# BEAMFORMER.net
KiCad netlist of a schematic drawn in Altium Designer
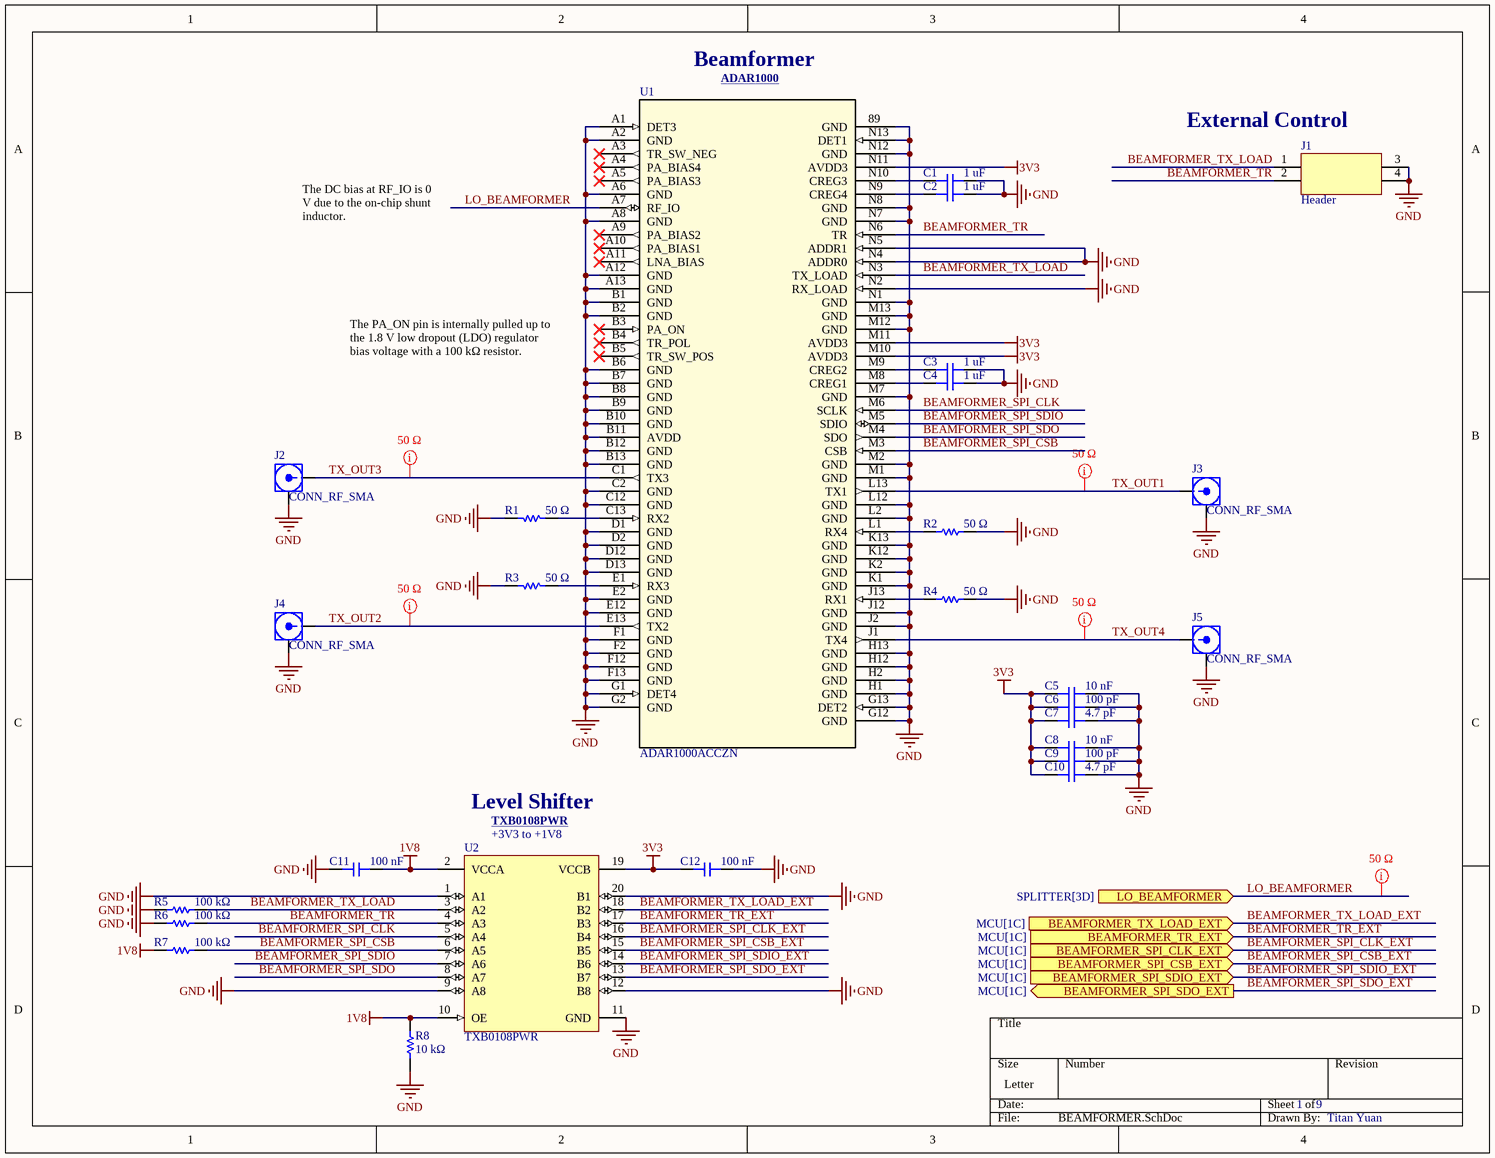
[diagram p0: BEAMFORMER.SchDoc]

(export (version "E")
  (design (tool "Eeschema 10.0.6"))
  (components
    (comp (ref "C1")
      (value "1 uF")
      (footprint "CAP_0603")
      (description "25V 1uF X7R ±10% 0603 Multilayer Ceramic Capacitors MLCC - SMD/SMT ROHS")
      (fields
        (field (name "MANUFACTURER") "Samsung Electro-Mechanics")
        (field (name "MANUFACTURER PART NUMBER") "CL10B105KA8NNNC")
      )
      (libsource (lib "Titan") (part "CAP"))
    )
    (comp (ref "C2")
      (value "1 uF")
      (footprint "CAP_0603")
      (description "25V 1uF X7R ±10% 0603 Multilayer Ceramic Capacitors MLCC - SMD/SMT ROHS")
      (fields
        (field (name "MANUFACTURER") "Samsung Electro-Mechanics")
        (field (name "MANUFACTURER PART NUMBER") "CL10B105KA8NNNC")
      )
      (libsource (lib "Titan") (part "CAP"))
    )
    (comp (ref "C3")
      (value "1 uF")
      (footprint "CAP_0603")
      (description "25V 1uF X7R ±10% 0603 Multilayer Ceramic Capacitors MLCC - SMD/SMT ROHS")
      (fields
        (field (name "MANUFACTURER") "Samsung Electro-Mechanics")
        (field (name "MANUFACTURER PART NUMBER") "CL10B105KA8NNNC")
      )
      (libsource (lib "Titan") (part "CAP"))
    )
    (comp (ref "C4")
      (value "1 uF")
      (footprint "CAP_0603")
      (description "25V 1uF X7R ±10% 0603 Multilayer Ceramic Capacitors MLCC - SMD/SMT ROHS")
      (fields
        (field (name "MANUFACTURER") "Samsung Electro-Mechanics")
        (field (name "MANUFACTURER PART NUMBER") "CL10B105KA8NNNC")
      )
      (libsource (lib "Titan") (part "CAP"))
    )
    (comp (ref "C5")
      (value "10 nF")
      (footprint "CAP_0402")
      (description "Multilayer Ceramic Capacitor, 0.01 uF, 25 V, ± 10%, X7R, 0402 [1005 Metric]")
      (fields
        (field (name "MANUFACTURER") "Murata Electronics")
        (field (name "MANUFACTURER PART NUMBER") "GRM155R71E103KA01D")
      )
      (libsource (lib "Titan") (part "CAP"))
    )
    (comp (ref "C6")
      (value "100 pF")
      (footprint "CAP_0402")
      (description "50V 100pF NP0 ±5% 0402 Multilayer Ceramic Capacitors MLCC - SMD/SMT ROHS")
      (fields
        (field (name "MANUFACTURER") "Yageo")
        (field (name "MANUFACTURER PART NUMBER") "CC0402JRNPO9BN101")
      )
      (libsource (lib "Titan") (part "CAP"))
    )
    (comp (ref "C7")
      (value "4.7 pF")
      (footprint "CAP_0402")
      (description "0402 4.7 pF 50 V ±0.25 pF Tolerance C0G SMT Multilayer Ceramic Capacitor")
      (fields
        (field (name "MANUFACTURER") "Murata Electronics")
        (field (name "MANUFACTURER PART NUMBER") "GRM1555C1H4R7CA01D")
      )
      (libsource (lib "Titan") (part "CAP"))
    )
    (comp (ref "C8")
      (value "10 nF")
      (footprint "CAP_0402")
      (description "Multilayer Ceramic Capacitor, 0.01 uF, 25 V, ± 10%, X7R, 0402 [1005 Metric]")
      (fields
        (field (name "MANUFACTURER") "Murata Electronics")
        (field (name "MANUFACTURER PART NUMBER") "GRM155R71E103KA01D")
      )
      (libsource (lib "Titan") (part "CAP"))
    )
    (comp (ref "C9")
      (value "100 pF")
      (footprint "CAP_0402")
      (description "50V 100pF NP0 ±5% 0402 Multilayer Ceramic Capacitors MLCC - SMD/SMT ROHS")
      (fields
        (field (name "MANUFACTURER") "Yageo")
        (field (name "MANUFACTURER PART NUMBER") "CC0402JRNPO9BN101")
      )
      (libsource (lib "Titan") (part "CAP"))
    )
    (comp (ref "C10")
      (value "4.7 pF")
      (footprint "CAP_0402")
      (description "0402 4.7 pF 50 V ±0.25 pF Tolerance C0G SMT Multilayer Ceramic Capacitor")
      (fields
        (field (name "MANUFACTURER") "Murata Electronics")
        (field (name "MANUFACTURER PART NUMBER") "GRM1555C1H4R7CA01D")
      )
      (libsource (lib "Titan") (part "CAP"))
    )
    (comp (ref "C11")
      (value "100 nF")
      (footprint "CAP_0402")
      (description "Ceramic Capacitor, Ceramic, 50V, 10% +Tol, 10% -Tol, X7R, 15% TC, 0.1uF, Surface Mount, 0402")
      (fields
        (field (name "MANUFACTURER") "Yageo")
        (field (name "MANUFACTURER PART NUMBER") "CC0402KPX7R9BB104")
      )
      (libsource (lib "Titan") (part "CAP"))
    )
    (comp (ref "C12")
      (value "100 nF")
      (footprint "CAP_0402")
      (description "Ceramic Capacitor, Ceramic, 50V, 10% +Tol, 10% -Tol, X7R, 15% TC, 0.1uF, Surface Mount, 0402")
      (fields
        (field (name "MANUFACTURER") "Yageo")
        (field (name "MANUFACTURER PART NUMBER") "CC0402KPX7R9BB104")
      )
      (libsource (lib "Titan") (part "CAP"))
    )
    (comp (ref "J1")
      (value "Header")
      (footprint "CONN_2x2_2.54mm_PinHeader_Vertical")
      (description "Pin Header, Board-to-Board, 2.54 mm, 2 Rows, 4 Contacts, Through Hole, TSW Series")
      (fields
        (field (name "MANUFACTURER") "Samtec")
        (field (name "MANUFACTURER PART NUMBER") "TSW-102-07-F-D")
      )
      (libsource (lib "Titan") (part "CONN_2x2_2.54mm_PinHeader_Vertical"))
    )
    (comp (ref "J2")
      (value "CONN_RF_SMA")
      (footprint "142-0701-801")
      (description "RF / Coaxial Connector, SMA Coaxial, Straight Jack, Solder, 50 ohm, Beryllium Copper")
      (fields
        (field (name "MANUFACTURER") "Cinch Connectivity Solutions Johnson")
        (field (name "MANUFACTURER PART NUMBER") "142-0701-801")
      )
      (libsource (lib "Titan") (part "CONN_RF_SMA"))
    )
    (comp (ref "J3")
      (value "CONN_RF_SMA")
      (footprint "142-0701-801")
      (description "RF / Coaxial Connector, SMA Coaxial, Straight Jack, Solder, 50 ohm, Beryllium Copper")
      (fields
        (field (name "MANUFACTURER") "Cinch Connectivity Solutions Johnson")
        (field (name "MANUFACTURER PART NUMBER") "142-0701-801")
      )
      (libsource (lib "Titan") (part "CONN_RF_SMA"))
    )
    (comp (ref "J4")
      (value "CONN_RF_SMA")
      (footprint "142-0701-801")
      (description "RF / Coaxial Connector, SMA Coaxial, Straight Jack, Solder, 50 ohm, Beryllium Copper")
      (fields
        (field (name "MANUFACTURER") "Cinch Connectivity Solutions Johnson")
        (field (name "MANUFACTURER PART NUMBER") "142-0701-801")
      )
      (libsource (lib "Titan") (part "CONN_RF_SMA"))
    )
    (comp (ref "J5")
      (value "CONN_RF_SMA")
      (footprint "142-0701-801")
      (description "RF / Coaxial Connector, SMA Coaxial, Straight Jack, Solder, 50 ohm, Beryllium Copper")
      (fields
        (field (name "MANUFACTURER") "Cinch Connectivity Solutions Johnson")
        (field (name "MANUFACTURER PART NUMBER") "142-0701-801")
      )
      (libsource (lib "Titan") (part "CONN_RF_SMA"))
    )
    (comp (ref "R1")
      (value "50 Ω")
      (footprint "RES_0402")
      (description "62.5mW Thin Film Resistor ±50ppm/℃ ±0.1% 50Ω 0402 Chip Resistor - Surface Mount ROHS")
      (fields
        (field (name "MANUFACTURER") "Yageo")
        (field (name "MANUFACTURER PART NUMBER") "RT0402BRE0750RL")
      )
      (libsource (lib "Titan") (part "RES"))
    )
    (comp (ref "R2")
      (value "50 Ω")
      (footprint "RES_0402")
      (description "62.5mW Thin Film Resistor ±50ppm/℃ ±0.1% 50Ω 0402 Chip Resistor - Surface Mount ROHS")
      (fields
        (field (name "MANUFACTURER") "Yageo")
        (field (name "MANUFACTURER PART NUMBER") "RT0402BRE0750RL")
      )
      (libsource (lib "Titan") (part "RES"))
    )
    (comp (ref "R3")
      (value "50 Ω")
      (footprint "RES_0402")
      (description "62.5mW Thin Film Resistor ±50ppm/℃ ±0.1% 50Ω 0402 Chip Resistor - Surface Mount ROHS")
      (fields
        (field (name "MANUFACTURER") "Yageo")
        (field (name "MANUFACTURER PART NUMBER") "RT0402BRE0750RL")
      )
      (libsource (lib "Titan") (part "RES"))
    )
    (comp (ref "R4")
      (value "50 Ω")
      (footprint "RES_0402")
      (description "62.5mW Thin Film Resistor ±50ppm/℃ ±0.1% 50Ω 0402 Chip Resistor - Surface Mount ROHS")
      (fields
        (field (name "MANUFACTURER") "Yageo")
        (field (name "MANUFACTURER PART NUMBER") "RT0402BRE0750RL")
      )
      (libsource (lib "Titan") (part "RES"))
    )
    (comp (ref "R5")
      (value "100 kΩ")
      (footprint "RES_0402")
      (description "Res General Purpose Thick Film 0402 100K Ohm 1% 1/16W ±100ppm/°C Molded SMD Paper T/R")
      (fields
        (field (name "MANUFACTURER") "Yageo")
        (field (name "MANUFACTURER PART NUMBER") "RC0402FR-07100KL")
      )
      (libsource (lib "Titan") (part "RES"))
    )
    (comp (ref "R6")
      (value "100 kΩ")
      (footprint "RES_0402")
      (description "Res General Purpose Thick Film 0402 100K Ohm 1% 1/16W ±100ppm/°C Molded SMD Paper T/R")
      (fields
        (field (name "MANUFACTURER") "Yageo")
        (field (name "MANUFACTURER PART NUMBER") "RC0402FR-07100KL")
      )
      (libsource (lib "Titan") (part "RES"))
    )
    (comp (ref "R7")
      (value "100 kΩ")
      (footprint "RES_0402")
      (description "Res General Purpose Thick Film 0402 100K Ohm 1% 1/16W ±100ppm/°C Molded SMD Paper T/R")
      (fields
        (field (name "MANUFACTURER") "Yageo")
        (field (name "MANUFACTURER PART NUMBER") "RC0402FR-07100KL")
      )
      (libsource (lib "Titan") (part "RES"))
    )
    (comp (ref "R8")
      (value "10 kΩ")
      (footprint "RES_0402")
      (description "Res Thick Film 0402 10K Ohm 1% 0.063W(1/16W) ±100ppm/C Pad SMD T/R")
      (fields
        (field (name "MANUFACTURER") "Yageo")
        (field (name "MANUFACTURER PART NUMBER") "RC0402FR-0710KL")
      )
      (libsource (lib "Titan") (part "RES"))
    )
    (comp (ref "U1")
      (value "ADAR1000ACCZN")
      (footprint "CC-88-1_ADI")
      (description "8 GHz to 16 GHz, 4-Channel, X Band and Ku Band Beamformer")
      (fields
        (field (name "MANUFACTURER") "Analog Devices")
        (field (name "COPYRIGHT") "Copyright (C) 2025 Ultra Librarian. All rights reserved.")
      )
      (libsource (lib "ADAR1000ACCZN") (part "ADAR1000ACCZN"))
    )
    (comp (ref "U2")
      (value "TXB0108PWR")
      (footprint "TXB0108PWR")
      (fields (field (name "MANUFACTURER") "Texas Instruments"))
      (libsource (lib "Titan") (part "TXB0108PWR"))
    )
  )
  (nets
    (net (code "1") (name "/BEAMFORMER_SPI_CLK") (class "Default")
      (node (ref "U1") (pin "M6") (pinfunction "SCLK_M6") (pintype "input"))
      (node (ref "U2") (pin "5") (pinfunction "A4_5") (pintype "bidirectional"))
    )
    (net (code "2") (name "/BEAMFORMER_SPI_CLK_EXT") (class "Default")
      (node (ref "U2") (pin "16") (pinfunction "B4_16") (pintype "bidirectional"))
    )
    (net (code "3") (name "/BEAMFORMER_SPI_CSB") (class "Default")
      (node (ref "R7") (pin "2") (pintype "passive"))
      (node (ref "U1") (pin "M3") (pinfunction "CSB_M3") (pintype "input"))
      (node (ref "U2") (pin "6") (pinfunction "A5_6") (pintype "bidirectional"))
    )
    (net (code "4") (name "/BEAMFORMER_SPI_CSB_EXT") (class "Default")
      (node (ref "U2") (pin "15") (pinfunction "B5_15") (pintype "bidirectional"))
    )
    (net (code "5") (name "/BEAMFORMER_SPI_SDIO") (class "Default")
      (node (ref "U1") (pin "M5") (pinfunction "SDIO_M5") (pintype "bidirectional"))
      (node (ref "U2") (pin "7") (pinfunction "A6_7") (pintype "bidirectional"))
    )
    (net (code "6") (name "/BEAMFORMER_SPI_SDIO_EXT") (class "Default")
      (node (ref "U2") (pin "14") (pinfunction "B6_14") (pintype "bidirectional"))
    )
    (net (code "7") (name "/BEAMFORMER_SPI_SDO") (class "Default")
      (node (ref "U1") (pin "M4") (pinfunction "SDO_M4") (pintype "output"))
      (node (ref "U2") (pin "8") (pinfunction "A7_8") (pintype "bidirectional"))
    )
    (net (code "8") (name "/BEAMFORMER_SPI_SDO_EXT") (class "Default")
      (node (ref "U2") (pin "13") (pinfunction "B7_13") (pintype "bidirectional"))
    )
    (net (code "9") (name "/BEAMFORMER_TR") (class "Default")
      (node (ref "J1") (pin "2") (pintype "passive"))
      (node (ref "R6") (pin "2") (pintype "passive"))
      (node (ref "U1") (pin "N6") (pinfunction "TR_N6") (pintype "input"))
      (node (ref "U2") (pin "4") (pinfunction "A3_4") (pintype "bidirectional"))
    )
    (net (code "10") (name "/BEAMFORMER_TR_EXT") (class "Default")
      (node (ref "U2") (pin "17") (pinfunction "B3_17") (pintype "bidirectional"))
    )
    (net (code "11") (name "/BEAMFORMER_TX_LOAD") (class "Default")
      (node (ref "J1") (pin "1") (pintype "passive"))
      (node (ref "R5") (pin "2") (pintype "passive"))
      (node (ref "U1") (pin "N3") (pinfunction "TX_LOAD_N3") (pintype "input"))
      (node (ref "U2") (pin "3") (pinfunction "A2_3") (pintype "bidirectional"))
    )
    (net (code "12") (name "/BEAMFORMER_TX_LOAD_EXT") (class "Default")
      (node (ref "U2") (pin "18") (pinfunction "B2_18") (pintype "bidirectional"))
    )
    (net (code "13") (name "/LO_BEAMFORMER") (class "Default")
      (node (ref "U1") (pin "A7") (pinfunction "RF_IO_A7") (pintype "bidirectional"))
    )
    (net (code "14") (name "/TX_OUT1") (class "Default")
      (node (ref "J3") (pin "1") (pintype "passive"))
      (node (ref "U1") (pin "L13") (pinfunction "TX1_L13") (pintype "output"))
    )
    (net (code "15") (name "/TX_OUT2") (class "Default")
      (node (ref "J4") (pin "1") (pintype "passive"))
      (node (ref "U1") (pin "E13") (pinfunction "TX2_E13") (pintype "output"))
    )
    (net (code "16") (name "/TX_OUT3") (class "Default")
      (node (ref "J2") (pin "1") (pintype "passive"))
      (node (ref "U1") (pin "C1") (pinfunction "TX3_C1") (pintype "output"))
    )
    (net (code "17") (name "/TX_OUT4") (class "Default")
      (node (ref "J5") (pin "1") (pintype "passive"))
      (node (ref "U1") (pin "J1") (pinfunction "TX4_J1") (pintype "output"))
    )
    (net (code "18") (name "1V8") (class "Default")
      (node (ref "C11") (pin "2") (pintype "passive"))
      (node (ref "R7") (pin "1") (pintype "passive"))
      (node (ref "R8") (pin "1") (pintype "passive"))
      (node (ref "U2") (pin "10") (pinfunction "OE_10") (pintype "input"))
      (node (ref "U2") (pin "2") (pinfunction "VCCA_2") (pintype "power_in"))
    )
    (net (code "19") (name "3V3") (class "Default")
      (node (ref "C10") (pin "1") (pintype "passive"))
      (node (ref "C12") (pin "1") (pintype "passive"))
      (node (ref "C5") (pin "1") (pintype "passive"))
      (node (ref "C6") (pin "2") (pintype "passive"))
      (node (ref "C7") (pin "1") (pintype "passive"))
      (node (ref "C8") (pin "1") (pintype "passive"))
      (node (ref "C9") (pin "2") (pintype "passive"))
      (node (ref "U1") (pin "M10") (pinfunction "AVDD3_M10") (pintype "power_in"))
      (node (ref "U1") (pin "M11") (pinfunction "AVDD3_M11") (pintype "power_in"))
      (node (ref "U1") (pin "N11") (pinfunction "AVDD3_N11") (pintype "power_in"))
      (node (ref "U2") (pin "19") (pinfunction "VCCB_19") (pintype "power_in"))
    )
    (net (code "20") (name "GND") (class "Default")
      (node (ref "C1") (pin "1") (pintype "passive"))
      (node (ref "C10") (pin "2") (pintype "passive"))
      (node (ref "C11") (pin "1") (pintype "passive"))
      (node (ref "C12") (pin "2") (pintype "passive"))
      (node (ref "C2") (pin "1") (pintype "passive"))
      (node (ref "C3") (pin "1") (pintype "passive"))
      (node (ref "C4") (pin "1") (pintype "passive"))
      (node (ref "C5") (pin "2") (pintype "passive"))
      (node (ref "C6") (pin "1") (pintype "passive"))
      (node (ref "C7") (pin "2") (pintype "passive"))
      (node (ref "C8") (pin "2") (pintype "passive"))
      (node (ref "C9") (pin "1") (pintype "passive"))
      (node (ref "J1") (pin "3") (pintype "passive"))
      (node (ref "J1") (pin "4") (pintype "passive"))
      (node (ref "J2") (pin "2") (pintype "passive"))
      (node (ref "J3") (pin "2") (pintype "passive"))
      (node (ref "J4") (pin "2") (pintype "passive"))
      (node (ref "J5") (pin "2") (pintype "passive"))
      (node (ref "R1") (pin "1") (pintype "passive"))
      (node (ref "R2") (pin "1") (pintype "passive"))
      (node (ref "R3") (pin "1") (pintype "passive"))
      (node (ref "R4") (pin "1") (pintype "passive"))
      (node (ref "R5") (pin "1") (pintype "passive"))
      (node (ref "R6") (pin "1") (pintype "passive"))
      (node (ref "R8") (pin "2") (pintype "passive"))
      (node (ref "U1") (pin "89") (pinfunction "GND_89") (pintype "power_in"))
      (node (ref "U1") (pin "A1") (pinfunction "DET3_A1") (pintype "input"))
      (node (ref "U1") (pin "A12") (pinfunction "GND_A12") (pintype "power_in"))
      (node (ref "U1") (pin "A13") (pinfunction "GND_A13") (pintype "power_in"))
      (node (ref "U1") (pin "A2") (pinfunction "GND_A2") (pintype "power_in"))
      (node (ref "U1") (pin "A6") (pinfunction "GND_A6") (pintype "power_in"))
      (node (ref "U1") (pin "A8") (pinfunction "GND_A8") (pintype "power_in"))
      (node (ref "U1") (pin "B1") (pinfunction "GND_B1") (pintype "power_in"))
      (node (ref "U1") (pin "B10") (pinfunction "GND_B10") (pintype "power_in"))
      (node (ref "U1") (pin "B11") (pinfunction "AVDD_B11") (pintype "power_in"))
      (node (ref "U1") (pin "B12") (pinfunction "GND_B12") (pintype "power_in"))
      (node (ref "U1") (pin "B13") (pinfunction "GND_B13") (pintype "power_in"))
      (node (ref "U1") (pin "B2") (pinfunction "GND_B2") (pintype "power_in"))
      (node (ref "U1") (pin "B6") (pinfunction "GND_B6") (pintype "power_in"))
      (node (ref "U1") (pin "B7") (pinfunction "GND_B7") (pintype "power_in"))
      (node (ref "U1") (pin "B8") (pinfunction "GND_B8") (pintype "power_in"))
      (node (ref "U1") (pin "B9") (pinfunction "GND_B9") (pintype "power_in"))
      (node (ref "U1") (pin "C12") (pinfunction "GND_C12") (pintype "power_in"))
      (node (ref "U1") (pin "C2") (pinfunction "GND_C2") (pintype "power_in"))
      (node (ref "U1") (pin "D1") (pinfunction "GND_D1") (pintype "power_in"))
      (node (ref "U1") (pin "D12") (pinfunction "GND_D12") (pintype "power_in"))
      (node (ref "U1") (pin "D13") (pinfunction "GND_D13") (pintype "power_in"))
      (node (ref "U1") (pin "D2") (pinfunction "GND_D2") (pintype "power_in"))
      (node (ref "U1") (pin "E12") (pinfunction "GND_E12") (pintype "power_in"))
      (node (ref "U1") (pin "E2") (pinfunction "GND_E2") (pintype "power_in"))
      (node (ref "U1") (pin "F1") (pinfunction "GND_F1") (pintype "power_in"))
      (node (ref "U1") (pin "F12") (pinfunction "GND_F12") (pintype "power_in"))
      (node (ref "U1") (pin "F13") (pinfunction "GND_F13") (pintype "power_in"))
      (node (ref "U1") (pin "F2") (pinfunction "GND_F2") (pintype "power_in"))
      (node (ref "U1") (pin "G1") (pinfunction "DET4_G1") (pintype "input"))
      (node (ref "U1") (pin "G12") (pinfunction "GND_G12") (pintype "power_in"))
      (node (ref "U1") (pin "G13") (pinfunction "DET2_G13") (pintype "input"))
      (node (ref "U1") (pin "G2") (pinfunction "GND_G2") (pintype "power_in"))
      (node (ref "U1") (pin "H1") (pinfunction "GND_H1") (pintype "power_in"))
      (node (ref "U1") (pin "H12") (pinfunction "GND_H12") (pintype "power_in"))
      (node (ref "U1") (pin "H13") (pinfunction "GND_H13") (pintype "power_in"))
      (node (ref "U1") (pin "H2") (pinfunction "GND_H2") (pintype "power_in"))
      (node (ref "U1") (pin "J12") (pinfunction "GND_J12") (pintype "power_in"))
      (node (ref "U1") (pin "J2") (pinfunction "GND_J2") (pintype "power_in"))
      (node (ref "U1") (pin "K1") (pinfunction "GND_K1") (pintype "power_in"))
      (node (ref "U1") (pin "K12") (pinfunction "GND_K12") (pintype "power_in"))
      (node (ref "U1") (pin "K13") (pinfunction "GND_K13") (pintype "power_in"))
      (node (ref "U1") (pin "K2") (pinfunction "GND_K2") (pintype "power_in"))
      (node (ref "U1") (pin "L12") (pinfunction "GND_L12") (pintype "power_in"))
      (node (ref "U1") (pin "L2") (pinfunction "GND_L2") (pintype "power_in"))
      (node (ref "U1") (pin "M1") (pinfunction "GND_M1") (pintype "power_in"))
      (node (ref "U1") (pin "M12") (pinfunction "GND_M12") (pintype "power_in"))
      (node (ref "U1") (pin "M13") (pinfunction "GND_M13") (pintype "power_in"))
      (node (ref "U1") (pin "M2") (pinfunction "GND_M2") (pintype "power_in"))
      (node (ref "U1") (pin "M7") (pinfunction "GND_M7") (pintype "power_in"))
      (node (ref "U1") (pin "N1") (pinfunction "GND_N1") (pintype "power_in"))
      (node (ref "U1") (pin "N12") (pinfunction "GND_N12") (pintype "power_in"))
      (node (ref "U1") (pin "N13") (pinfunction "DET1_N13") (pintype "input"))
      (node (ref "U1") (pin "N2") (pinfunction "RX_LOAD_N2") (pintype "input"))
      (node (ref "U1") (pin "N4") (pinfunction "ADDR0_N4") (pintype "input"))
      (node (ref "U1") (pin "N5") (pinfunction "ADDR1_N5") (pintype "input"))
      (node (ref "U1") (pin "N7") (pinfunction "GND_N7") (pintype "power_in"))
      (node (ref "U1") (pin "N8") (pinfunction "GND_N8") (pintype "power_in"))
      (node (ref "U2") (pin "1") (pinfunction "A1_1") (pintype "bidirectional"))
      (node (ref "U2") (pin "11") (pinfunction "GND_11") (pintype "power_in"))
      (node (ref "U2") (pin "12") (pinfunction "B8_12") (pintype "bidirectional"))
      (node (ref "U2") (pin "20") (pinfunction "B1_20") (pintype "bidirectional"))
      (node (ref "U2") (pin "9") (pinfunction "A8_9") (pintype "bidirectional"))
    )
    (net (code "21") (name "Net-(U1-CREG1)") (class "Default")
      (node (ref "C4") (pin "2") (pintype "passive"))
      (node (ref "U1") (pin "M8") (pinfunction "CREG1_M8") (pintype "power_in"))
    )
    (net (code "22") (name "Net-(U1-CREG2)") (class "Default")
      (node (ref "C3") (pin "2") (pintype "passive"))
      (node (ref "U1") (pin "M9") (pinfunction "CREG2_M9") (pintype "power_in"))
    )
    (net (code "23") (name "Net-(U1-CREG3)") (class "Default")
      (node (ref "C1") (pin "2") (pintype "passive"))
      (node (ref "U1") (pin "N10") (pinfunction "CREG3_N10") (pintype "power_in"))
    )
    (net (code "24") (name "Net-(U1-CREG4)") (class "Default")
      (node (ref "C2") (pin "2") (pintype "passive"))
      (node (ref "U1") (pin "N9") (pinfunction "CREG4_N9") (pintype "power_in"))
    )
    (net (code "25") (name "Net-(U1-RX1)") (class "Default")
      (node (ref "R4") (pin "2") (pintype "passive"))
      (node (ref "U1") (pin "J13") (pinfunction "RX1_J13") (pintype "input"))
    )
    (net (code "26") (name "Net-(U1-RX2)") (class "Default")
      (node (ref "R1") (pin "2") (pintype "passive"))
      (node (ref "U1") (pin "C13") (pinfunction "RX2_C13") (pintype "input"))
    )
    (net (code "27") (name "Net-(U1-RX3)") (class "Default")
      (node (ref "R3") (pin "2") (pintype "passive"))
      (node (ref "U1") (pin "E1") (pinfunction "RX3_E1") (pintype "input"))
    )
    (net (code "28") (name "Net-(U1-RX4)") (class "Default")
      (node (ref "R2") (pin "2") (pintype "passive"))
      (node (ref "U1") (pin "L1") (pinfunction "RX4_L1") (pintype "input"))
    )
    (net (code "29") (name "unconnected-(U1-LNA_BIAS-PadA11)") (class "Default")
      (node (ref "U1") (pin "A11") (pinfunction "LNA_BIAS_A11") (pintype "output+no_connect"))
    )
    (net (code "30") (name "unconnected-(U1-PA_BIAS1-PadA10)") (class "Default")
      (node (ref "U1") (pin "A10") (pinfunction "PA_BIAS1_A10") (pintype "output+no_connect"))
    )
    (net (code "31") (name "unconnected-(U1-PA_BIAS2-PadA9)") (class "Default")
      (node (ref "U1") (pin "A9") (pinfunction "PA_BIAS2_A9") (pintype "output+no_connect"))
    )
    (net (code "32") (name "unconnected-(U1-PA_BIAS3-PadA5)") (class "Default")
      (node (ref "U1") (pin "A5") (pinfunction "PA_BIAS3_A5") (pintype "output+no_connect"))
    )
    (net (code "33") (name "unconnected-(U1-PA_BIAS4-PadA4)") (class "Default")
      (node (ref "U1") (pin "A4") (pinfunction "PA_BIAS4_A4") (pintype "output+no_connect"))
    )
    (net (code "34") (name "unconnected-(U1-PA_ON-PadB3)") (class "Default")
      (node (ref "U1") (pin "B3") (pinfunction "PA_ON_B3") (pintype "input+no_connect"))
    )
    (net (code "35") (name "unconnected-(U1-TR_POL-PadB4)") (class "Default")
      (node (ref "U1") (pin "B4") (pinfunction "TR_POL_B4") (pintype "output+no_connect"))
    )
    (net (code "36") (name "unconnected-(U1-TR_SW_NEG-PadA3)") (class "Default")
      (node (ref "U1") (pin "A3") (pinfunction "TR_SW_NEG_A3") (pintype "output+no_connect"))
    )
    (net (code "37") (name "unconnected-(U1-TR_SW_POS-PadB5)") (class "Default")
      (node (ref "U1") (pin "B5") (pinfunction "TR_SW_POS_B5") (pintype "output+no_connect"))
    )
  )
)
